# Connectors.net
KiCad netlist of a schematic drawn in Altium Designer
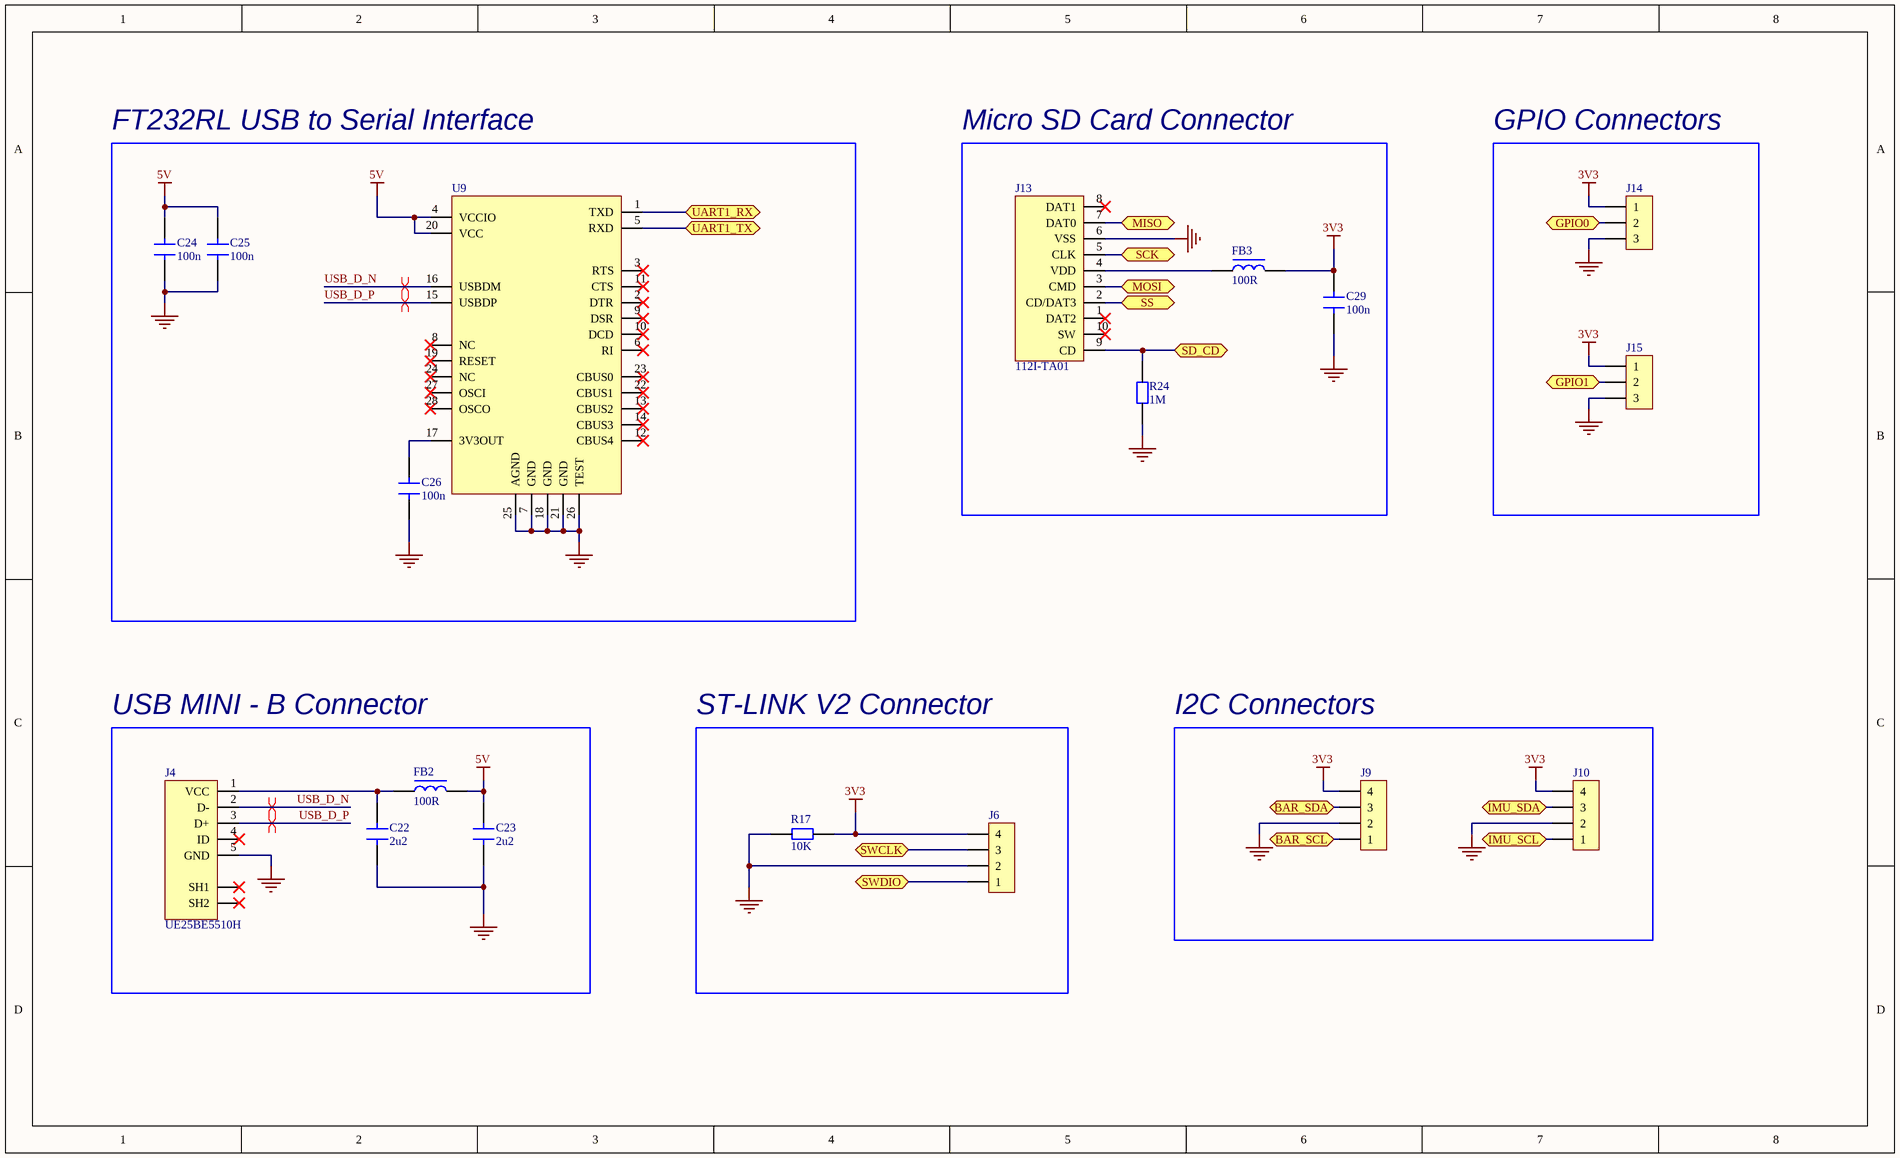
[diagram p0: Connectors.SchDoc]

(export (version "E")
  (design (tool "Eeschema 10.0.6"))
  (components
    (comp (ref "C22")
      (value "2u2")
      (footprint "CAP 0805")
      (description "Capacitor SMD 0805 25V")
      (libsource (lib "Schlib") (part "CAP 0805 25V"))
    )
    (comp (ref "C23")
      (value "2u2")
      (footprint "CAP 0805")
      (description "Capacitor SMD 0805 25V")
      (libsource (lib "Schlib") (part "CAP 0805 25V"))
    )
    (comp (ref "C24")
      (value "100n")
      (footprint "CAP 0603")
      (description "Capacitor SMD 0603 50V")
      (libsource (lib "Schlib") (part "CAP 0603 50V"))
    )
    (comp (ref "C25")
      (value "100n")
      (footprint "CAP 0603")
      (description "Capacitor SMD 0603 50V")
      (libsource (lib "Schlib") (part "CAP 0603 50V"))
    )
    (comp (ref "C26")
      (value "100n")
      (footprint "CAP 0603")
      (description "Capacitor SMD 0603 50V")
      (libsource (lib "Schlib") (part "CAP 0603 50V"))
    )
    (comp (ref "C29")
      (value "100n")
      (footprint "CAP 0603")
      (description "Capacitor SMD 0603 50V")
      (libsource (lib "Schlib") (part "CAP 0603 50V"))
    )
    (comp (ref "FB2")
      (value "100R")
      (footprint "FB 0805")
      (description "Ferrite Bead SMD 0805")
      (libsource (lib "Schlib") (part "FB 0805"))
    )
    (comp (ref "FB3")
      (value "100R")
      (footprint "FB 0603")
      (description "Ferrite Bead SMD 0603")
      (libsource (lib "Schlib") (part "FB 0603"))
    )
    (comp (ref "J4")
      (value "UE25BE5510H")
      (footprint "UE25BE55H")
      (description "Conn Mini USB 2.0 Type B RCP 5 POS 0.8mm Solder ST Thru-Hole 5 Terminal 1 Port")
      (fields (field (name "MANUFACTURER") "Amphenol Commercial"))
      (libsource (lib "Schlib") (part "UE25BE5510H"))
    )
    (comp (ref "J6")
      (value "1x4 HEADER MALE")
      (footprint "1X4 HEADER MALE")
      (libsource (lib "Schlib") (part "1x4 HEADER MALE"))
    )
    (comp (ref "J9")
      (value "1x4 HEADER MALE")
      (footprint "1X4 HEADER MALE")
      (libsource (lib "Schlib") (part "1x4 HEADER MALE"))
    )
    (comp (ref "J10")
      (value "1x4 HEADER MALE")
      (footprint "1X4 HEADER MALE")
      (libsource (lib "Schlib") (part "1x4 HEADER MALE"))
    )
    (comp (ref "J13")
      (value "112I-TA01")
      (footprint "112I-TA01")
      (description "Micro SD Card Push-Pull 10P (8+2), Switch, Peg, SMD 112I-TA01")
      (libsource (lib "Schlib") (part "112I-TA01"))
    )
    (comp (ref "J14")
      (value "JST B3B-XH-A")
      (footprint "JST_B3B-XH-A")
      (description "Connector Header, XH Series, 3 Position, 2.50mm, Through Hole, Press-Fit, Solder, Natural")
      (fields
        (field (name "MANUFACTURER") "JST")
        (field (name "MANUFACTURER PART NUMBER") "B3B-XH-A(LF)(SN)")
      )
      (libsource (lib "Schlib") (part "JST B3B-XH-A"))
    )
    (comp (ref "J15")
      (value "JST B3B-XH-A")
      (footprint "JST_B3B-XH-A")
      (description "Connector Header, XH Series, 3 Position, 2.50mm, Through Hole, Press-Fit, Solder, Natural")
      (fields
        (field (name "MANUFACTURER") "JST")
        (field (name "MANUFACTURER PART NUMBER") "B3B-XH-A(LF)(SN)")
      )
      (libsource (lib "Schlib") (part "JST B3B-XH-A"))
    )
    (comp (ref "R17")
      (value "10K")
      (footprint "RES 0603")
      (description "Resistor SMD 0603")
      (libsource (lib "Schlib") (part "RES 0603"))
    )
    (comp (ref "R24")
      (value "1M")
      (footprint "RES 0603")
      (description "Resistor SMD 0603")
      (libsource (lib "Schlib") (part "RES 0603"))
    )
    (comp (ref "U9")
      (value "FT232RL-REEL")
      (footprint "FT232RL")
      (description "IC USB FS SERIAL UART 28-SSOP")
      (fields (field (name "MANUFACTURER") "FTDI") (field (name "VOLTAGE") "5V"))
      (libsource (lib "Schlib") (part "FT232RL-REEL"))
    )
  )
  (nets
    (net (code "1") (name "/BAR_SCL") (class "Default")
      (node (ref "J9") (pin "1") (pinfunction "1_1") (pintype "passive"))
    )
    (net (code "2") (name "/BAR_SDA") (class "Default")
      (node (ref "J9") (pin "3") (pinfunction "3_3") (pintype "passive"))
    )
    (net (code "3") (name "/GPIO0") (class "Default")
      (node (ref "J14") (pin "2") (pinfunction "2_2") (pintype "passive"))
    )
    (net (code "4") (name "/GPIO1") (class "Default")
      (node (ref "J15") (pin "2") (pinfunction "2_2") (pintype "passive"))
    )
    (net (code "5") (name "/IMU_SCL") (class "Default")
      (node (ref "J10") (pin "1") (pinfunction "1_1") (pintype "passive"))
    )
    (net (code "6") (name "/IMU_SDA") (class "Default")
      (node (ref "J10") (pin "3") (pinfunction "3_3") (pintype "passive"))
    )
    (net (code "7") (name "/MISO") (class "Default")
      (node (ref "J13") (pin "7") (pinfunction "DAT0_7") (pintype "passive"))
    )
    (net (code "8") (name "/MOSI") (class "Default")
      (node (ref "J13") (pin "3") (pinfunction "CMD_3") (pintype "passive"))
    )
    (net (code "9") (name "/SCK") (class "Default")
      (node (ref "J13") (pin "5") (pinfunction "CLK_5") (pintype "passive"))
    )
    (net (code "10") (name "/SD_CD") (class "Default")
      (node (ref "J13") (pin "9") (pinfunction "CD_9") (pintype "passive"))
      (node (ref "R24") (pin "2") (pinfunction "2_2") (pintype "passive"))
    )
    (net (code "11") (name "/SS") (class "Default")
      (node (ref "J13") (pin "2") (pinfunction "CD/DAT3_2") (pintype "passive"))
    )
    (net (code "12") (name "/SWCLK") (class "Default")
      (node (ref "J6") (pin "3") (pinfunction "3_3") (pintype "passive"))
    )
    (net (code "13") (name "/SWDIO") (class "Default")
      (node (ref "J6") (pin "1") (pinfunction "1_1") (pintype "passive"))
    )
    (net (code "14") (name "/UART1_RX") (class "Default")
      (node (ref "U9") (pin "1") (pinfunction "TXD_1") (pintype "passive"))
    )
    (net (code "15") (name "/UART1_TX") (class "Default")
      (node (ref "U9") (pin "5") (pinfunction "RXD_5") (pintype "passive"))
    )
    (net (code "16") (name "/USB_D_N") (class "Default")
      (node (ref "J4") (pin "2") (pinfunction "D-_2") (pintype "passive"))
      (node (ref "U9") (pin "16") (pinfunction "USBDM_16") (pintype "passive"))
    )
    (net (code "17") (name "/USB_D_P") (class "Default")
      (node (ref "J4") (pin "3") (pinfunction "D+_3") (pintype "passive"))
      (node (ref "U9") (pin "15") (pinfunction "USBDP_15") (pintype "passive"))
    )
    (net (code "18") (name "3V3") (class "Default")
      (node (ref "C29") (pin "2") (pinfunction "2_2") (pintype "passive"))
      (node (ref "FB3") (pin "2") (pintype "passive"))
      (node (ref "J10") (pin "4") (pinfunction "4_4") (pintype "passive"))
      (node (ref "J14") (pin "1") (pinfunction "1_1") (pintype "passive"))
      (node (ref "J15") (pin "1") (pinfunction "1_1") (pintype "passive"))
      (node (ref "J6") (pin "4") (pinfunction "4_4") (pintype "passive"))
      (node (ref "J9") (pin "4") (pinfunction "4_4") (pintype "passive"))
      (node (ref "R17") (pin "2") (pinfunction "2_2") (pintype "passive"))
    )
    (net (code "19") (name "5V") (class "Default")
      (node (ref "C23") (pin "2") (pinfunction "2_2") (pintype "passive"))
      (node (ref "C24") (pin "2") (pinfunction "2_2") (pintype "passive"))
      (node (ref "C25") (pin "2") (pinfunction "2_2") (pintype "passive"))
      (node (ref "FB2") (pin "2") (pintype "passive"))
      (node (ref "U9") (pin "20") (pinfunction "VCC_20") (pintype "passive"))
      (node (ref "U9") (pin "4") (pinfunction "VCCIO_4") (pintype "passive"))
    )
    (net (code "20") (name "GND") (class "Default")
      (node (ref "C22") (pin "1") (pinfunction "1_1") (pintype "passive"))
      (node (ref "C23") (pin "1") (pinfunction "1_1") (pintype "passive"))
      (node (ref "C24") (pin "1") (pinfunction "1_1") (pintype "passive"))
      (node (ref "C25") (pin "1") (pinfunction "1_1") (pintype "passive"))
      (node (ref "C26") (pin "1") (pinfunction "1_1") (pintype "passive"))
      (node (ref "C29") (pin "1") (pinfunction "1_1") (pintype "passive"))
      (node (ref "J10") (pin "2") (pinfunction "2_2") (pintype "passive"))
      (node (ref "J13") (pin "6") (pinfunction "VSS_6") (pintype "passive"))
      (node (ref "J14") (pin "3") (pinfunction "3_3") (pintype "passive"))
      (node (ref "J15") (pin "3") (pinfunction "3_3") (pintype "passive"))
      (node (ref "J4") (pin "5") (pinfunction "GND_5") (pintype "passive"))
      (node (ref "J6") (pin "2") (pinfunction "2_2") (pintype "passive"))
      (node (ref "J9") (pin "2") (pinfunction "2_2") (pintype "passive"))
      (node (ref "R17") (pin "1") (pinfunction "1_1") (pintype "passive"))
      (node (ref "R24") (pin "1") (pinfunction "1_1") (pintype "passive"))
      (node (ref "U9") (pin "18") (pinfunction "GND_18") (pintype "passive"))
      (node (ref "U9") (pin "21") (pinfunction "GND_21") (pintype "passive"))
      (node (ref "U9") (pin "25") (pinfunction "AGND_25") (pintype "passive"))
      (node (ref "U9") (pin "26") (pinfunction "TEST_26") (pintype "passive"))
      (node (ref "U9") (pin "7") (pinfunction "GND_7") (pintype "passive"))
    )
    (net (code "21") (name "Net-(J4-VCC)") (class "Default")
      (node (ref "C22") (pin "2") (pinfunction "2_2") (pintype "passive"))
      (node (ref "FB2") (pin "1") (pintype "passive"))
      (node (ref "J4") (pin "1") (pinfunction "VCC_1") (pintype "passive"))
    )
    (net (code "22") (name "Net-(J13-VDD)") (class "Default")
      (node (ref "FB3") (pin "1") (pintype "passive"))
      (node (ref "J13") (pin "4") (pinfunction "VDD_4") (pintype "passive"))
    )
    (net (code "23") (name "Net-(U9-3V3OUT)") (class "Default")
      (node (ref "C26") (pin "2") (pinfunction "2_2") (pintype "passive"))
      (node (ref "U9") (pin "17") (pinfunction "3V3OUT_17") (pintype "passive"))
    )
    (net (code "24") (name "unconnected-(J4-ID-Pad4)") (class "Default")
      (node (ref "J4") (pin "4") (pinfunction "ID_4") (pintype "passive+no_connect"))
    )
    (net (code "25") (name "unconnected-(J4-PadSH1)") (class "Default")
      (node (ref "J4") (pin "SH1") (pinfunction "SH1_SH1") (pintype "passive+no_connect"))
    )
    (net (code "26") (name "unconnected-(J4-PadSH2)") (class "Default")
      (node (ref "J4") (pin "SH2") (pinfunction "SH2_SH2") (pintype "passive+no_connect"))
    )
    (net (code "27") (name "unconnected-(J13-DAT1-Pad8)") (class "Default")
      (node (ref "J13") (pin "8") (pinfunction "DAT1_8") (pintype "passive+no_connect"))
    )
    (net (code "28") (name "unconnected-(J13-DAT2-Pad1)") (class "Default")
      (node (ref "J13") (pin "1") (pinfunction "DAT2_1") (pintype "passive+no_connect"))
    )
    (net (code "29") (name "unconnected-(J13-SW-Pad10)") (class "Default")
      (node (ref "J13") (pin "10") (pinfunction "SW_10") (pintype "passive+no_connect"))
    )
    (net (code "30") (name "unconnected-(U9-CBUS0-Pad23)") (class "Default")
      (node (ref "U9") (pin "23") (pinfunction "CBUS0_23") (pintype "passive+no_connect"))
    )
    (net (code "31") (name "unconnected-(U9-CBUS1-Pad22)") (class "Default")
      (node (ref "U9") (pin "22") (pinfunction "CBUS1_22") (pintype "passive+no_connect"))
    )
    (net (code "32") (name "unconnected-(U9-CBUS2-Pad13)") (class "Default")
      (node (ref "U9") (pin "13") (pinfunction "CBUS2_13") (pintype "passive+no_connect"))
    )
    (net (code "33") (name "unconnected-(U9-CBUS3-Pad14)") (class "Default")
      (node (ref "U9") (pin "14") (pinfunction "CBUS3_14") (pintype "passive+no_connect"))
    )
    (net (code "34") (name "unconnected-(U9-CBUS4-Pad12)") (class "Default")
      (node (ref "U9") (pin "12") (pinfunction "CBUS4_12") (pintype "passive+no_connect"))
    )
    (net (code "35") (name "unconnected-(U9-CTS-Pad11)") (class "Default")
      (node (ref "U9") (pin "11") (pinfunction "CTS_11") (pintype "passive+no_connect"))
    )
    (net (code "36") (name "unconnected-(U9-DCD-Pad10)") (class "Default")
      (node (ref "U9") (pin "10") (pinfunction "DCD_10") (pintype "passive+no_connect"))
    )
    (net (code "37") (name "unconnected-(U9-DSR-Pad9)") (class "Default")
      (node (ref "U9") (pin "9") (pinfunction "DSR_9") (pintype "passive+no_connect"))
    )
    (net (code "38") (name "unconnected-(U9-DTR-Pad2)") (class "Default")
      (node (ref "U9") (pin "2") (pinfunction "DTR_2") (pintype "passive+no_connect"))
    )
    (net (code "39") (name "unconnected-(U9-NC-Pad8)") (class "Default")
      (node (ref "U9") (pin "8") (pinfunction "NC_8") (pintype "passive+no_connect"))
    )
    (net (code "40") (name "unconnected-(U9-NC-Pad24)") (class "Default")
      (node (ref "U9") (pin "24") (pinfunction "NC_24") (pintype "passive+no_connect"))
    )
    (net (code "41") (name "unconnected-(U9-OSCI-Pad27)") (class "Default")
      (node (ref "U9") (pin "27") (pinfunction "OSCI_27") (pintype "passive+no_connect"))
    )
    (net (code "42") (name "unconnected-(U9-OSCO-Pad28)") (class "Default")
      (node (ref "U9") (pin "28") (pinfunction "OSCO_28") (pintype "passive+no_connect"))
    )
    (net (code "43") (name "unconnected-(U9-RESET-Pad19)") (class "Default")
      (node (ref "U9") (pin "19") (pinfunction "RESET_19") (pintype "passive+no_connect"))
    )
    (net (code "44") (name "unconnected-(U9-RI-Pad6)") (class "Default")
      (node (ref "U9") (pin "6") (pinfunction "RI_6") (pintype "passive+no_connect"))
    )
    (net (code "45") (name "unconnected-(U9-RTS-Pad3)") (class "Default")
      (node (ref "U9") (pin "3") (pinfunction "RTS_3") (pintype "passive+no_connect"))
    )
  )
)
